# power.net
KiCad netlist of a schematic drawn in EAGLE
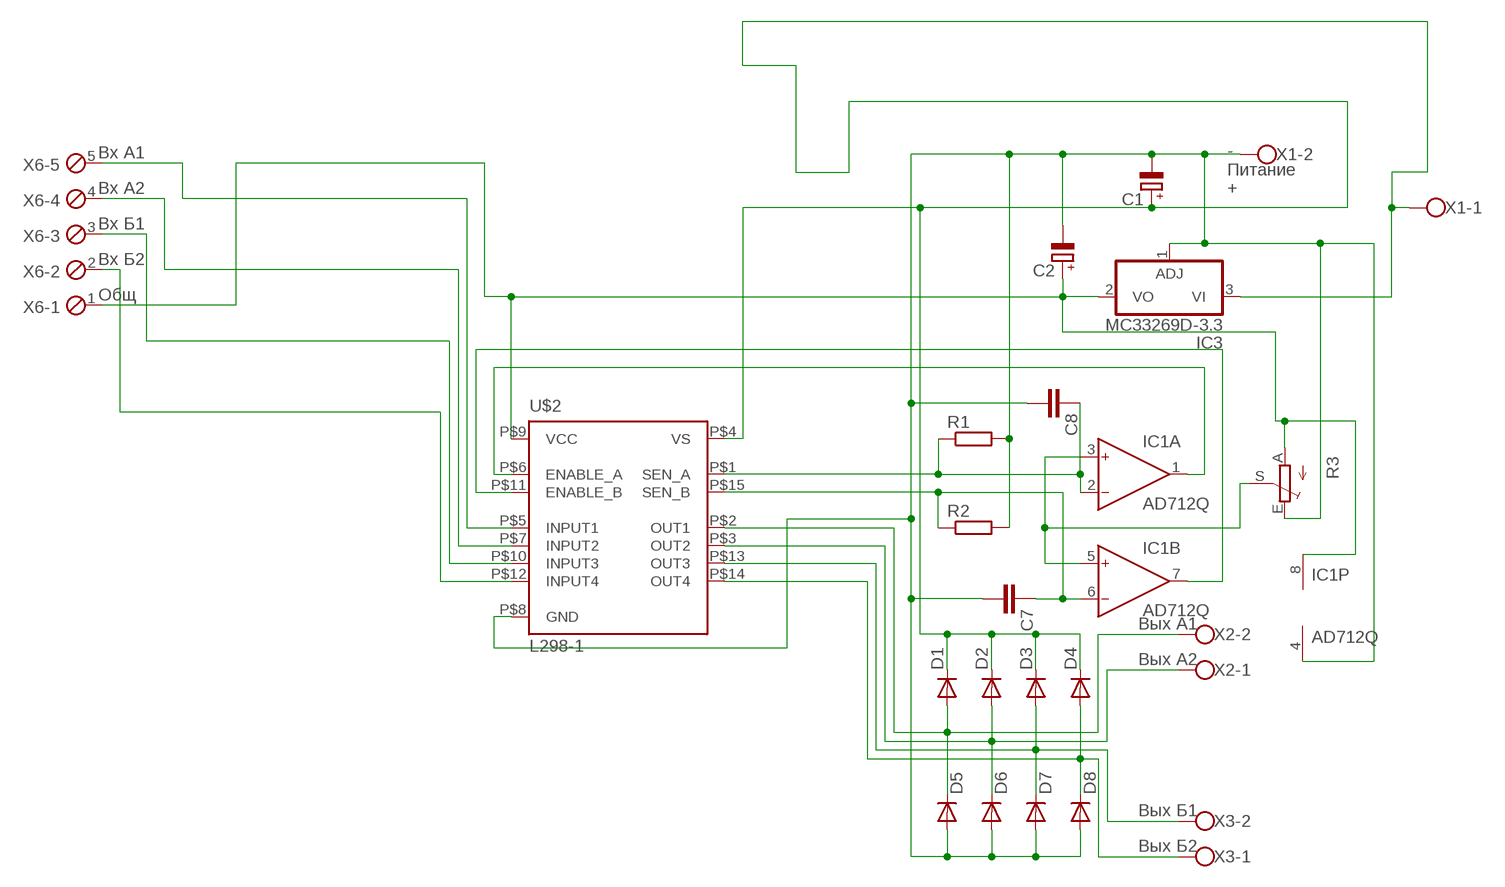
[diagram p0: schematic, sheet 1]

(export (version "E")
  (design (tool "Eeschema 10.0.6"))
  (components
    (comp (ref "C1")
      (value "CPOL-EUE2,5-6E")
      (footprint "eagle-import:E2,5-6E")
      (libsource (lib "eagle-import") (part "CPOL-EUE2,5-6E"))
    )
    (comp (ref "C2")
      (value "CPOL-EUE2,5-6E")
      (footprint "eagle-import:E2,5-6E")
      (libsource (lib "eagle-import") (part "CPOL-EUE2,5-6E"))
    )
    (comp (ref "C7")
      (value "C-EUC1206")
      (footprint "eagle-import:C1206")
      (libsource (lib "eagle-import") (part "C-EUC1206"))
    )
    (comp (ref "C8")
      (value "C-EUC1206")
      (footprint "eagle-import:C1206")
      (libsource (lib "eagle-import") (part "C-EUC1206"))
    )
    (comp (ref "D1")
      (value "DIODE-C1702-05")
      (footprint "eagle-import:C1702-05")
      (libsource (lib "eagle-import") (part "DIODE-C1702-05"))
    )
    (comp (ref "D2")
      (value "DIODE-C1702-05")
      (footprint "eagle-import:C1702-05")
      (libsource (lib "eagle-import") (part "DIODE-C1702-05"))
    )
    (comp (ref "D3")
      (value "DIODE-C1702-05")
      (footprint "eagle-import:C1702-05")
      (libsource (lib "eagle-import") (part "DIODE-C1702-05"))
    )
    (comp (ref "D4")
      (value "DIODE-C1702-05")
      (footprint "eagle-import:C1702-05")
      (libsource (lib "eagle-import") (part "DIODE-C1702-05"))
    )
    (comp (ref "D5")
      (value "DIODE-C1702-05")
      (footprint "eagle-import:C1702-05")
      (libsource (lib "eagle-import") (part "DIODE-C1702-05"))
    )
    (comp (ref "D6")
      (value "DIODE-C1702-05")
      (footprint "eagle-import:C1702-05")
      (libsource (lib "eagle-import") (part "DIODE-C1702-05"))
    )
    (comp (ref "D7")
      (value "DIODE-C1702-05")
      (footprint "eagle-import:C1702-05")
      (libsource (lib "eagle-import") (part "DIODE-C1702-05"))
    )
    (comp (ref "D8")
      (value "DIODE-C1702-05")
      (footprint "eagle-import:C1702-05")
      (libsource (lib "eagle-import") (part "DIODE-C1702-05"))
    )
    (comp (ref "IC1")
      (value "AD712Q")
      (footprint "eagle-import:DIL08")
      (fields (field (name "MF") "ALTERA CORPORATION") (field (name "MPN") "AD712AQ"))
      (libsource (lib "eagle-import") (part "AD712Q"))
    )
    (comp (ref "IC3")
      (value "MC33269D-3.3")
      (footprint "eagle-import:DPACK")
      (libsource (lib "eagle-import") (part "MC33269?D-3.3"))
    )
    (comp (ref "R1")
      (value "R-EU_VTA52")
      (footprint "eagle-import:VTA52")
      (libsource (lib "eagle-import") (part "R-EU_VTA52"))
    )
    (comp (ref "R2")
      (value "R-EU_VTA52")
      (footprint "eagle-import:VTA52")
      (libsource (lib "eagle-import") (part "R-EU_VTA52"))
    )
    (comp (ref "R3")
      (value "TRIM_EU-S75H")
      (footprint "eagle-import:S75H")
      (libsource (lib "eagle-import") (part "TRIM_EU-S75H"))
    )
    (comp (ref "U$2")
      (value "L298-1")
      (footprint "eagle-import:MULTIWATT-15-1")
      (libsource (lib "eagle-import") (part "L298-1"))
    )
    (comp (ref "X1")
      (value "W237-102")
      (footprint "eagle-import:W237-102")
      (fields (field (name "MPN") "237-102"))
      (libsource (lib "eagle-import") (part "W237-102"))
    )
    (comp (ref "X2")
      (value "W237-102")
      (footprint "eagle-import:W237-102")
      (fields (field (name "MPN") "237-102"))
      (libsource (lib "eagle-import") (part "W237-102"))
    )
    (comp (ref "X3")
      (value "W237-102")
      (footprint "eagle-import:W237-102")
      (fields (field (name "MPN") "237-102"))
      (libsource (lib "eagle-import") (part "W237-102"))
    )
    (comp (ref "X6")
      (value "MPT5")
      (footprint "eagle-import:5POL254")
      (libsource (lib "eagle-import") (part "MPT5"))
    )
  )
  (nets
    (net (code "1") (name "Net-(IC1A-IN+)") (class "Default")
      (node (ref "IC1") (pin "3") (pinfunction "IN+_3") (pintype "input"))
      (node (ref "IC1") (pin "5") (pinfunction "IN+_5") (pintype "input"))
      (node (ref "R3") (pin "S") (pinfunction "S_S") (pintype "passive"))
    )
    (net (code "2") (name "Net-(IC1A-IN-)") (class "Default")
      (node (ref "C8") (pin "1") (pinfunction "1_1") (pintype "passive"))
      (node (ref "IC1") (pin "2") (pinfunction "IN-_2") (pintype "input"))
      (node (ref "R1") (pin "1") (pinfunction "1_1") (pintype "passive"))
      (node (ref "U$2") (pin "P$1") (pinfunction "SEN_A_P$1") (pintype "input"))
    )
    (net (code "3") (name "Net-(IC1A-OUT)") (class "Default")
      (node (ref "IC1") (pin "1") (pinfunction "OUT_1") (pintype "output"))
      (node (ref "U$2") (pin "P$6") (pinfunction "ENABLE_A_P$6") (pintype "input"))
    )
    (net (code "4") (name "Net-(IC1B-IN-)") (class "Default")
      (node (ref "C7") (pin "1") (pinfunction "1_1") (pintype "passive"))
      (node (ref "IC1") (pin "6") (pinfunction "IN-_6") (pintype "input"))
      (node (ref "R2") (pin "1") (pinfunction "1_1") (pintype "passive"))
      (node (ref "U$2") (pin "P$15") (pinfunction "SEN_B_P$15") (pintype "input"))
    )
    (net (code "5") (name "Net-(IC1B-OUT)") (class "Default")
      (node (ref "IC1") (pin "7") (pinfunction "OUT_7") (pintype "output"))
      (node (ref "U$2") (pin "P$11") (pinfunction "ENABLE_B_P$11") (pintype "input"))
    )
    (net (code "6") (name "Net-(IC1C-V+)") (class "Default")
      (node (ref "C2") (pin "+") (pinfunction "+_+") (pintype "passive"))
      (node (ref "IC1") (pin "8") (pinfunction "V+_8") (pintype "power_in"))
      (node (ref "IC3") (pin "2") (pinfunction "VO_2") (pintype "passive"))
      (node (ref "R3") (pin "A") (pinfunction "A_A") (pintype "passive"))
      (node (ref "U$2") (pin "P$9") (pinfunction "VCC_P$9") (pintype "power_in"))
      (node (ref "X6") (pin "1") (pinfunction "1_1") (pintype "passive"))
    )
    (net (code "7") (name "Net-(IC1C-V-)") (class "Default")
      (node (ref "C1") (pin "-") (pinfunction "-_-") (pintype "passive"))
      (node (ref "C2") (pin "-") (pinfunction "-_-") (pintype "passive"))
      (node (ref "C7") (pin "2") (pinfunction "2_2") (pintype "passive"))
      (node (ref "C8") (pin "2") (pinfunction "2_2") (pintype "passive"))
      (node (ref "D5") (pin "A") (pinfunction "A_A") (pintype "passive"))
      (node (ref "D6") (pin "A") (pinfunction "A_A") (pintype "passive"))
      (node (ref "D7") (pin "A") (pinfunction "A_A") (pintype "passive"))
      (node (ref "D8") (pin "A") (pinfunction "A_A") (pintype "passive"))
      (node (ref "IC1") (pin "4") (pinfunction "V-_4") (pintype "power_in"))
      (node (ref "IC3") (pin "1") (pinfunction "ADJ_1") (pintype "input"))
      (node (ref "R1") (pin "2") (pinfunction "2_2") (pintype "passive"))
      (node (ref "R2") (pin "2") (pinfunction "2_2") (pintype "passive"))
      (node (ref "R3") (pin "E") (pinfunction "E_E") (pintype "passive"))
      (node (ref "U$2") (pin "P$8") (pinfunction "GND_P$8") (pintype "power_in"))
      (node (ref "X1") (pin "2") (pinfunction "KL_2") (pintype "passive"))
    )
    (net (code "8") (name "Net-(IC3-VI)") (class "Default")
      (node (ref "C1") (pin "+") (pinfunction "+_+") (pintype "passive"))
      (node (ref "D1") (pin "C") (pinfunction "C_C") (pintype "passive"))
      (node (ref "D2") (pin "C") (pinfunction "C_C") (pintype "passive"))
      (node (ref "D3") (pin "C") (pinfunction "C_C") (pintype "passive"))
      (node (ref "D4") (pin "C") (pinfunction "C_C") (pintype "passive"))
      (node (ref "IC3") (pin "3") (pinfunction "VI_3") (pintype "input"))
      (node (ref "U$2") (pin "P$4") (pinfunction "VS_P$4") (pintype "power_in"))
      (node (ref "X1") (pin "1") (pinfunction "KL_1") (pintype "passive"))
    )
    (net (code "9") (name "Net-(U$2-INPUT1)") (class "Default")
      (node (ref "U$2") (pin "P$5") (pinfunction "INPUT1_P$5") (pintype "input"))
      (node (ref "X6") (pin "5") (pinfunction "1_5") (pintype "passive"))
    )
    (net (code "10") (name "Net-(U$2-INPUT2)") (class "Default")
      (node (ref "U$2") (pin "P$7") (pinfunction "INPUT2_P$7") (pintype "input"))
      (node (ref "X6") (pin "4") (pinfunction "1_4") (pintype "passive"))
    )
    (net (code "11") (name "Net-(U$2-INPUT3)") (class "Default")
      (node (ref "U$2") (pin "P$10") (pinfunction "INPUT3_P$10") (pintype "input"))
      (node (ref "X6") (pin "3") (pinfunction "1_3") (pintype "passive"))
    )
    (net (code "12") (name "Net-(U$2-INPUT4)") (class "Default")
      (node (ref "U$2") (pin "P$12") (pinfunction "INPUT4_P$12") (pintype "input"))
      (node (ref "X6") (pin "2") (pinfunction "1_2") (pintype "passive"))
    )
    (net (code "13") (name "Net-(U$2-OUT1)") (class "Default")
      (node (ref "D1") (pin "A") (pinfunction "A_A") (pintype "passive"))
      (node (ref "D5") (pin "C") (pinfunction "C_C") (pintype "passive"))
      (node (ref "U$2") (pin "P$2") (pinfunction "OUT1_P$2") (pintype "output"))
      (node (ref "X2") (pin "2") (pinfunction "KL_2") (pintype "passive"))
    )
    (net (code "14") (name "Net-(U$2-OUT2)") (class "Default")
      (node (ref "D2") (pin "A") (pinfunction "A_A") (pintype "passive"))
      (node (ref "D6") (pin "C") (pinfunction "C_C") (pintype "passive"))
      (node (ref "U$2") (pin "P$3") (pinfunction "OUT2_P$3") (pintype "output"))
      (node (ref "X2") (pin "1") (pinfunction "KL_1") (pintype "passive"))
    )
    (net (code "15") (name "Net-(U$2-OUT3)") (class "Default")
      (node (ref "D3") (pin "A") (pinfunction "A_A") (pintype "passive"))
      (node (ref "D7") (pin "C") (pinfunction "C_C") (pintype "passive"))
      (node (ref "U$2") (pin "P$13") (pinfunction "OUT3_P$13") (pintype "output"))
      (node (ref "X3") (pin "2") (pinfunction "KL_2") (pintype "passive"))
    )
    (net (code "16") (name "Net-(U$2-OUT4)") (class "Default")
      (node (ref "D4") (pin "A") (pinfunction "A_A") (pintype "passive"))
      (node (ref "D8") (pin "C") (pinfunction "C_C") (pintype "passive"))
      (node (ref "U$2") (pin "P$14") (pinfunction "OUT4_P$14") (pintype "output"))
      (node (ref "X3") (pin "1") (pinfunction "KL_1") (pintype "passive"))
    )
  )
)
